# CTExciter.net
KiCad netlist of a schematic drawn in EAGLE
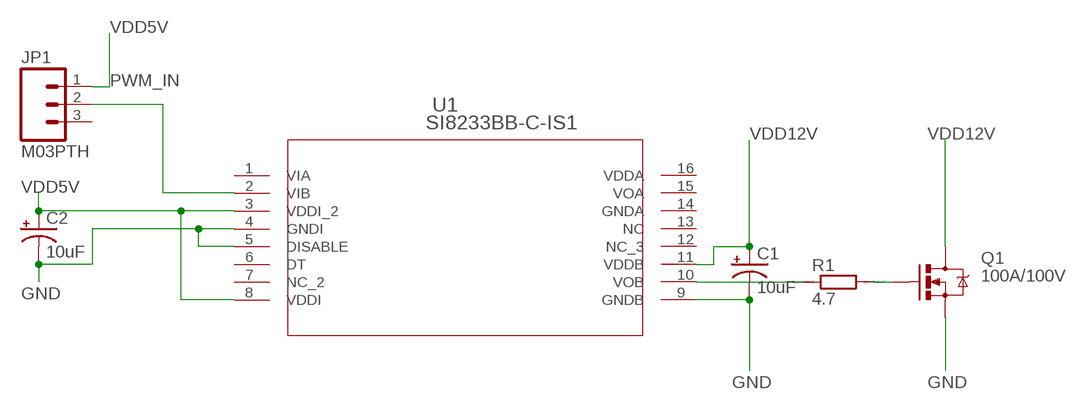
[diagram p0: schematic, sheet 1]

(export (version "E")
  (design (tool "Eeschema 10.0.6"))
  (components
    (comp (ref "C1")
      (value "10uF")
      (footprint "eagle-import:CPOL-RADIAL-10UF-25V")
      (libsource (lib "eagle-import") (part "CAP_POLPTH2"))
    )
    (comp (ref "C2")
      (value "10uF")
      (footprint "eagle-import:CPOL-RADIAL-10UF-25V")
      (libsource (lib "eagle-import") (part "CAP_POLPTH2"))
    )
    (comp (ref "JP1")
      (value "M03PTH")
      (footprint "eagle-import:1X03")
      (libsource (lib "eagle-import") (part "M03PTH"))
    )
    (comp (ref "Q1")
      (value "100A/100V")
      (footprint "eagle-import:TO-263_D2PAK")
      (libsource (lib "eagle-import") (part "MOSFET-NCHANNELPSMN7R0"))
    )
    (comp (ref "R1")
      (value "4.7")
      (footprint "eagle-import:R0805")
      (libsource (lib "eagle-import") (part "R"))
    )
    (comp (ref "U1")
      (value "SI8233BB-C-IS1")
      (footprint "eagle-import:SOIC-16")
      (libsource (lib "eagle-import") (part "SI8233BB-C-IS1"))
    )
  )
  (nets
    (net (code "1") (name "/GND") (class "Default")
      (node (ref "C1") (pin "2") (pinfunction "-_2") (pintype "passive"))
      (node (ref "C2") (pin "2") (pinfunction "-_2") (pintype "passive"))
      (node (ref "Q1") (pin "3") (pinfunction "S_3") (pintype "passive"))
      (node (ref "U1") (pin "4") (pinfunction "GNDI_4") (pintype "passive"))
      (node (ref "U1") (pin "5") (pinfunction "DISABLE_5") (pintype "input"))
      (node (ref "U1") (pin "9") (pinfunction "GNDB_9") (pintype "passive"))
    )
    (net (code "2") (name "/PWM_IN") (class "Default")
      (node (ref "JP1") (pin "2") (pinfunction "2_2") (pintype "passive"))
      (node (ref "U1") (pin "2") (pinfunction "VIB_2") (pintype "input"))
    )
    (net (code "3") (name "/VDD5V") (class "Default")
      (node (ref "C2") (pin "1") (pinfunction "+_1") (pintype "passive"))
      (node (ref "JP1") (pin "1") (pinfunction "1_1") (pintype "passive"))
      (node (ref "U1") (pin "3") (pinfunction "VDDI_2_3") (pintype "passive"))
      (node (ref "U1") (pin "8") (pinfunction "VDDI_8") (pintype "passive"))
    )
    (net (code "4") (name "/VDD12V") (class "Default")
      (node (ref "C1") (pin "1") (pinfunction "+_1") (pintype "passive"))
      (node (ref "Q1") (pin "2") (pinfunction "D_2") (pintype "passive"))
      (node (ref "U1") (pin "11") (pinfunction "VDDB_11") (pintype "passive"))
    )
    (net (code "5") (name "Net-(Q1-G)") (class "Default")
      (node (ref "Q1") (pin "1") (pinfunction "G_1") (pintype "passive"))
      (node (ref "R1") (pin "2") (pinfunction "2_2") (pintype "passive"))
    )
    (net (code "6") (name "Net-(U1-VOB)") (class "Default")
      (node (ref "R1") (pin "1") (pinfunction "1_1") (pintype "passive"))
      (node (ref "U1") (pin "10") (pinfunction "VOB_10") (pintype "output"))
    )
    (net (code "7") (name "unconnected-(JP1-Pad3)") (class "Default")
      (node (ref "JP1") (pin "3") (pinfunction "3_3") (pintype "passive"))
    )
    (net (code "8") (name "unconnected-(U1-DT-Pad6)") (class "Default")
      (node (ref "U1") (pin "6") (pinfunction "DT_6") (pintype "input"))
    )
    (net (code "9") (name "unconnected-(U1-GNDA-Pad14)") (class "Default")
      (node (ref "U1") (pin "14") (pinfunction "GNDA_14") (pintype "passive"))
    )
    (net (code "10") (name "unconnected-(U1-NC-Pad13)") (class "Default")
      (node (ref "U1") (pin "13") (pinfunction "NC_13") (pintype "no_connect"))
    )
    (net (code "11") (name "unconnected-(U1-NC_2-Pad7)") (class "Default")
      (node (ref "U1") (pin "7") (pinfunction "NC_2_7") (pintype "no_connect"))
    )
    (net (code "12") (name "unconnected-(U1-NC_3-Pad12)") (class "Default")
      (node (ref "U1") (pin "12") (pinfunction "NC_3_12") (pintype "no_connect"))
    )
    (net (code "13") (name "unconnected-(U1-VDDA-Pad16)") (class "Default")
      (node (ref "U1") (pin "16") (pinfunction "VDDA_16") (pintype "passive"))
    )
    (net (code "14") (name "unconnected-(U1-VIA-Pad1)") (class "Default")
      (node (ref "U1") (pin "1") (pinfunction "VIA_1") (pintype "input"))
    )
    (net (code "15") (name "unconnected-(U1-VOA-Pad15)") (class "Default")
      (node (ref "U1") (pin "15") (pinfunction "VOA_15") (pintype "output"))
    )
  )
)
